# PCB_triggerELP.net
KiCad netlist of a schematic drawn in EAGLE
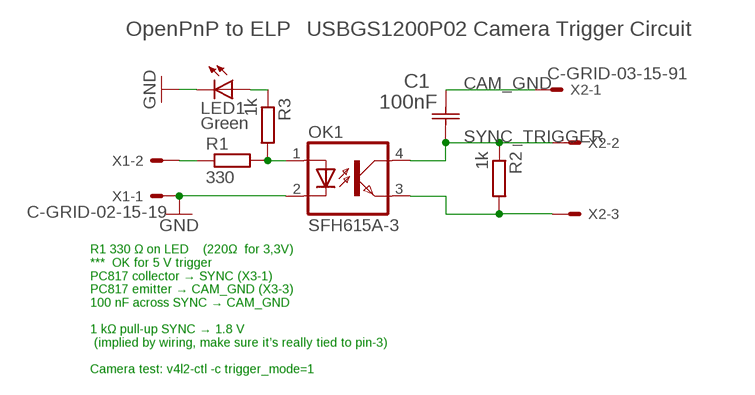
[diagram p0: schematic, sheet 1]

(export (version "E")
  (design (tool "Eeschema 10.0.6"))
  (components
    (comp (ref "C1")
      (value "100nF")
      (footprint "eagle-import:CAPC2012X140N")
      (fields (field (name "MPN") "0805YC474MA72A") (field (name "TOLERANCE") "±20%"))
      (libsource (lib "eagle-import") (part "0805YC474MA72A"))
    )
    (comp (ref "LED1")
      (value "Green")
      (footprint "eagle-import:CHIP-LED0603")
      (libsource (lib "eagle-import") (part "LEDCHIP-LED0603"))
    )
    (comp (ref "OK1")
      (value "SFH615A-3")
      (footprint "eagle-import:SMD4-7")
      (fields (field (name "MF") "VISHAY/TELEFUNKEN") (field (name "MPN") "SFH6186-3"))
      (libsource (lib "eagle-import") (part "SFH618?6-3"))
    )
    (comp (ref "R1")
      (value "330")
      (footprint "eagle-import:R0603")
      (libsource (lib "eagle-import") (part "R-EU_R0603"))
    )
    (comp (ref "R2")
      (value "1k")
      (footprint "eagle-import:R0603")
      (libsource (lib "eagle-import") (part "R-EU_R0603"))
    )
    (comp (ref "R3")
      (value "1k")
      (footprint "eagle-import:R0603")
      (libsource (lib "eagle-import") (part "R-EU_R0603"))
    )
    (comp (ref "X1")
      (value "C-GRID-02-15-19")
      (footprint "eagle-import:15-91-02")
      (libsource (lib "eagle-import") (part "C-GRID-02-15-19"))
    )
    (comp (ref "X2")
      (value "C-GRID-03-15-91")
      (footprint "eagle-import:15-91-03")
      (libsource (lib "eagle-import") (part "C-GRID-03-15-91"))
    )
  )
  (nets
    (net (code "1") (name "/CAM_GND") (class "Default")
      (node (ref "C1") (pin "2") (pinfunction "C2_2") (pintype "passive"))
      (node (ref "X2") (pin "1") (pinfunction "S_1") (pintype "passive"))
    )
    (net (code "2") (name "/SYNC_TRIGGER") (class "Default")
      (node (ref "C1") (pin "1") (pinfunction "C1_1") (pintype "passive"))
      (node (ref "OK1") (pin "4") (pinfunction "COL_4") (pintype "passive"))
      (node (ref "R2") (pin "1") (pinfunction "1_1") (pintype "passive"))
      (node (ref "X2") (pin "2") (pinfunction "S_2") (pintype "passive"))
    )
    (net (code "3") (name "GND") (class "Default")
      (node (ref "LED1") (pin "C") (pinfunction "C_C") (pintype "passive"))
      (node (ref "OK1") (pin "2") (pinfunction "C_2") (pintype "passive"))
      (node (ref "X1") (pin "1") (pinfunction "S_1") (pintype "passive"))
    )
    (net (code "4") (name "Net-(LED1-PadA)") (class "Default")
      (node (ref "LED1") (pin "A") (pinfunction "A_A") (pintype "passive"))
      (node (ref "R3") (pin "1") (pinfunction "1_1") (pintype "passive"))
    )
    (net (code "5") (name "Net-(OK1-A)") (class "Default")
      (node (ref "OK1") (pin "1") (pinfunction "A_1") (pintype "passive"))
      (node (ref "R1") (pin "2") (pinfunction "2_2") (pintype "passive"))
      (node (ref "R3") (pin "2") (pinfunction "2_2") (pintype "passive"))
    )
    (net (code "6") (name "Net-(OK1-EMIT)") (class "Default")
      (node (ref "OK1") (pin "3") (pinfunction "EMIT_3") (pintype "passive"))
      (node (ref "R2") (pin "2") (pinfunction "2_2") (pintype "passive"))
      (node (ref "X2") (pin "3") (pinfunction "S_3") (pintype "passive"))
    )
    (net (code "7") (name "Net-(X1B-S)") (class "Default")
      (node (ref "R1") (pin "1") (pinfunction "1_1") (pintype "passive"))
      (node (ref "X1") (pin "2") (pinfunction "S_2") (pintype "passive"))
    )
  )
)
